# ICSP.net
KiCad netlist of a schematic drawn in Altium Designer
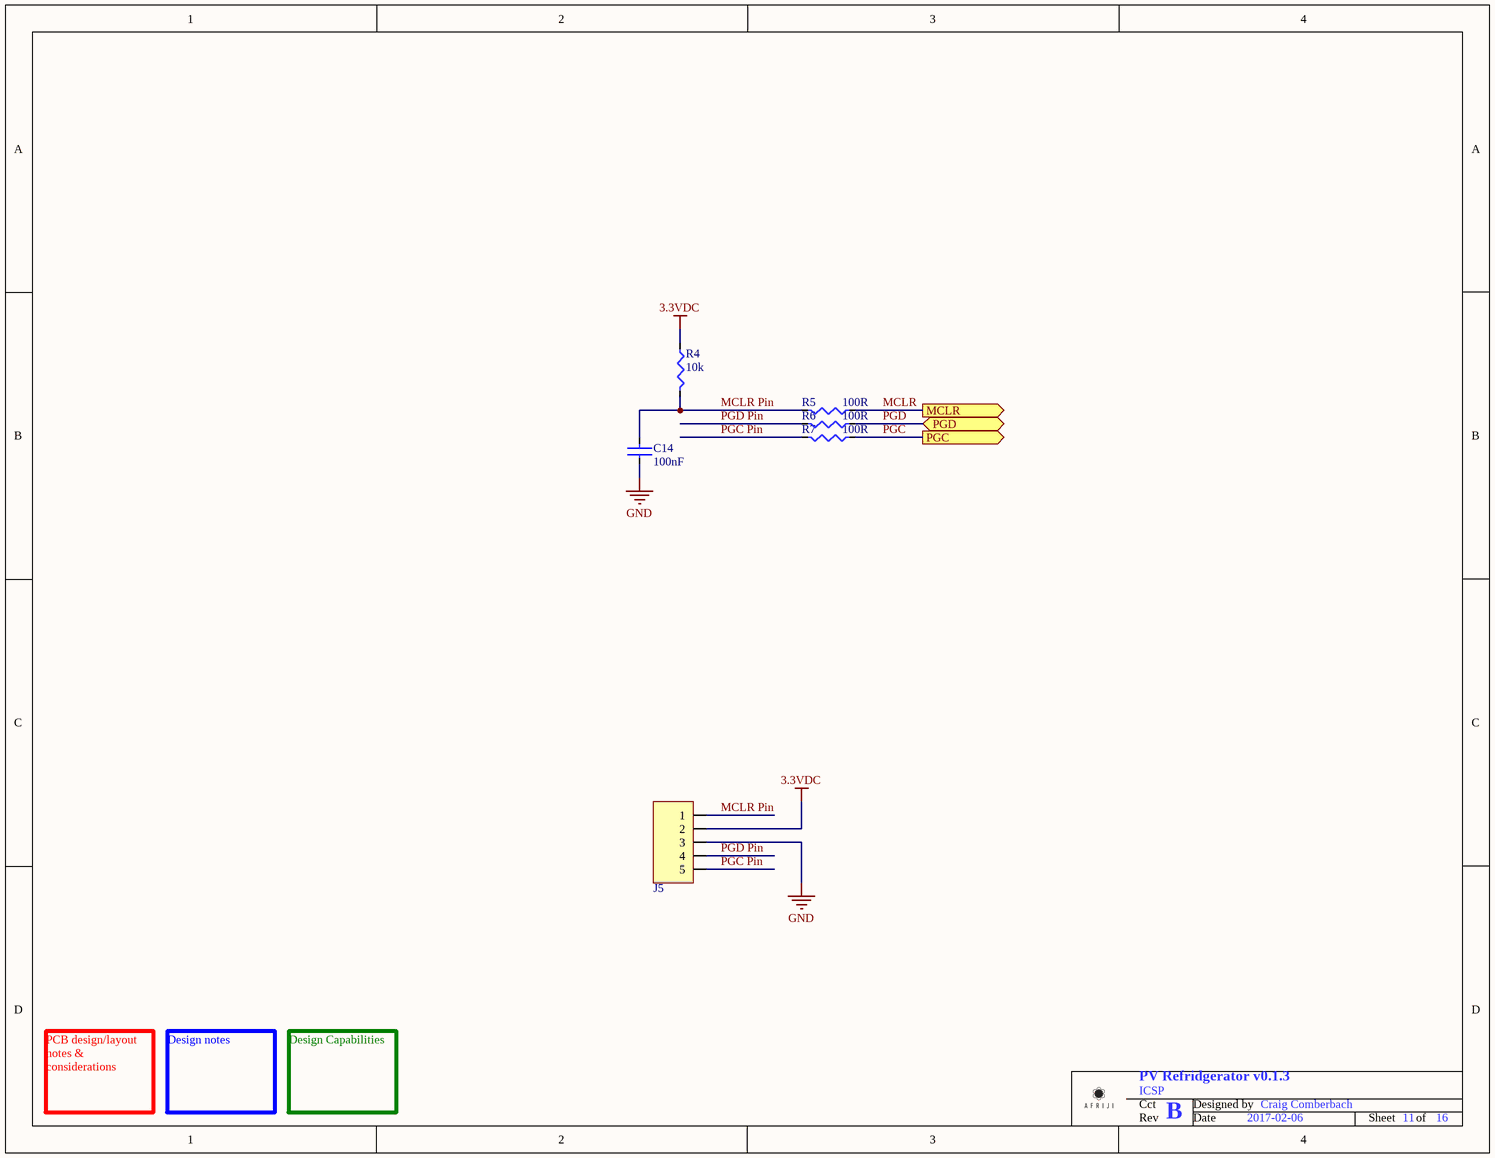
[diagram p0: ICSP.SchDoc]

(export (version "E")
  (design (tool "Eeschema 10.0.6"))
  (components
    (comp (ref "C14")
      (value "100nF 0603 50V")
      (footprint "C0603 - Ceramic")
      (fields
        (field (name "MANUFACTURER") "Samsung Electro-Mechanics America, Inc")
        (field (name "MANUFACTURER PART NUMBER") "CL10B104KB8SFNC")
        (field (name "TOLERANCE") "±10%")
        (field (name "CAPACITANCE") "100nF")
      )
      (libsource (lib "Personal Library") (part "100nF 0603 50V"))
    )
    (comp (ref "J5")
      (value "MTA100 - 5-Pin with friction Lock")
      (footprint "Connector - MTA-100 5 Position")
      (description "Flash Programmer")
      (fields
        (field (name "MANUFACTURER") "TE Connectivity")
        (field (name "MANUFACTURER PART NUMBER") "640456-5")
      )
      (libsource (lib "Local Library") (part "MTA100 - 5-Pin with friction Lock"))
    )
    (comp (ref "R4")
      (value "10k 0603 1%")
      (footprint "R0603")
      (description "Resistor")
      (fields
        (field (name "MANUFACTURER") "Yageo")
        (field (name "MANUFACTURER PART NUMBER") "RC0603FR-0710KL")
        (field (name "RESISTANCE (OHMS)") "10k")
      )
      (libsource (lib "Personal Library") (part "10k 0603 1%"))
    )
    (comp (ref "R5")
      (value "100R 0603 1%")
      (footprint "R0603")
      (description "1/8W")
      (fields
        (field (name "MANUFACTURER") "Yageo")
        (field (name "MANUFACTURER PART NUMBER") "RC0603FR-07100RL")
        (field (name "RESISTANCE (OHMS)") "100R")
      )
      (libsource (lib "Personal Library") (part "100R 0603 1%"))
    )
    (comp (ref "R6")
      (value "100R 0603 1%")
      (footprint "R0603")
      (description "1/8W")
      (fields
        (field (name "MANUFACTURER") "Yageo")
        (field (name "MANUFACTURER PART NUMBER") "RC0603FR-07100RL")
        (field (name "RESISTANCE (OHMS)") "100R")
      )
      (libsource (lib "Personal Library") (part "100R 0603 1%"))
    )
    (comp (ref "R7")
      (value "100R 0603 1%")
      (footprint "R0603")
      (description "1/8W")
      (fields
        (field (name "MANUFACTURER") "Yageo")
        (field (name "MANUFACTURER PART NUMBER") "RC0603FR-07100RL")
        (field (name "RESISTANCE (OHMS)") "100R")
      )
      (libsource (lib "Personal Library") (part "100R 0603 1%"))
    )
  )
  (nets
    (net (code "1") (name "/MCLR") (class "Default")
      (node (ref "R5") (pin "2") (pinfunction "2_2") (pintype "passive"))
    )
    (net (code "2") (name "/MCLR Pin") (class "Default")
      (node (ref "C14") (pin "1") (pinfunction "1_1") (pintype "passive"))
      (node (ref "J5") (pin "1") (pinfunction "1_1") (pintype "passive"))
      (node (ref "R4") (pin "2") (pinfunction "2_2") (pintype "passive"))
      (node (ref "R5") (pin "1") (pinfunction "1_1") (pintype "passive"))
    )
    (net (code "3") (name "/PGC") (class "Default")
      (node (ref "R7") (pin "2") (pinfunction "2_2") (pintype "passive"))
    )
    (net (code "4") (name "/PGC Pin") (class "Default")
      (node (ref "J5") (pin "5") (pinfunction "5_5") (pintype "passive"))
      (node (ref "R7") (pin "1") (pinfunction "1_1") (pintype "passive"))
    )
    (net (code "5") (name "/PGD") (class "Default")
      (node (ref "R6") (pin "2") (pinfunction "2_2") (pintype "passive"))
    )
    (net (code "6") (name "/PGD Pin") (class "Default")
      (node (ref "J5") (pin "4") (pinfunction "4_4") (pintype "passive"))
      (node (ref "R6") (pin "1") (pinfunction "1_1") (pintype "passive"))
    )
    (net (code "7") (name "3.3VDC") (class "Default")
      (node (ref "J5") (pin "2") (pinfunction "2_2") (pintype "passive"))
      (node (ref "R4") (pin "1") (pinfunction "1_1") (pintype "passive"))
    )
    (net (code "8") (name "GND") (class "Default")
      (node (ref "C14") (pin "2") (pinfunction "2_2") (pintype "passive"))
      (node (ref "J5") (pin "3") (pinfunction "3_3") (pintype "passive"))
    )
  )
)
